# 2_pure60-WKL_matrix.net
KiCad netlist of a schematic drawn in Altium Designer
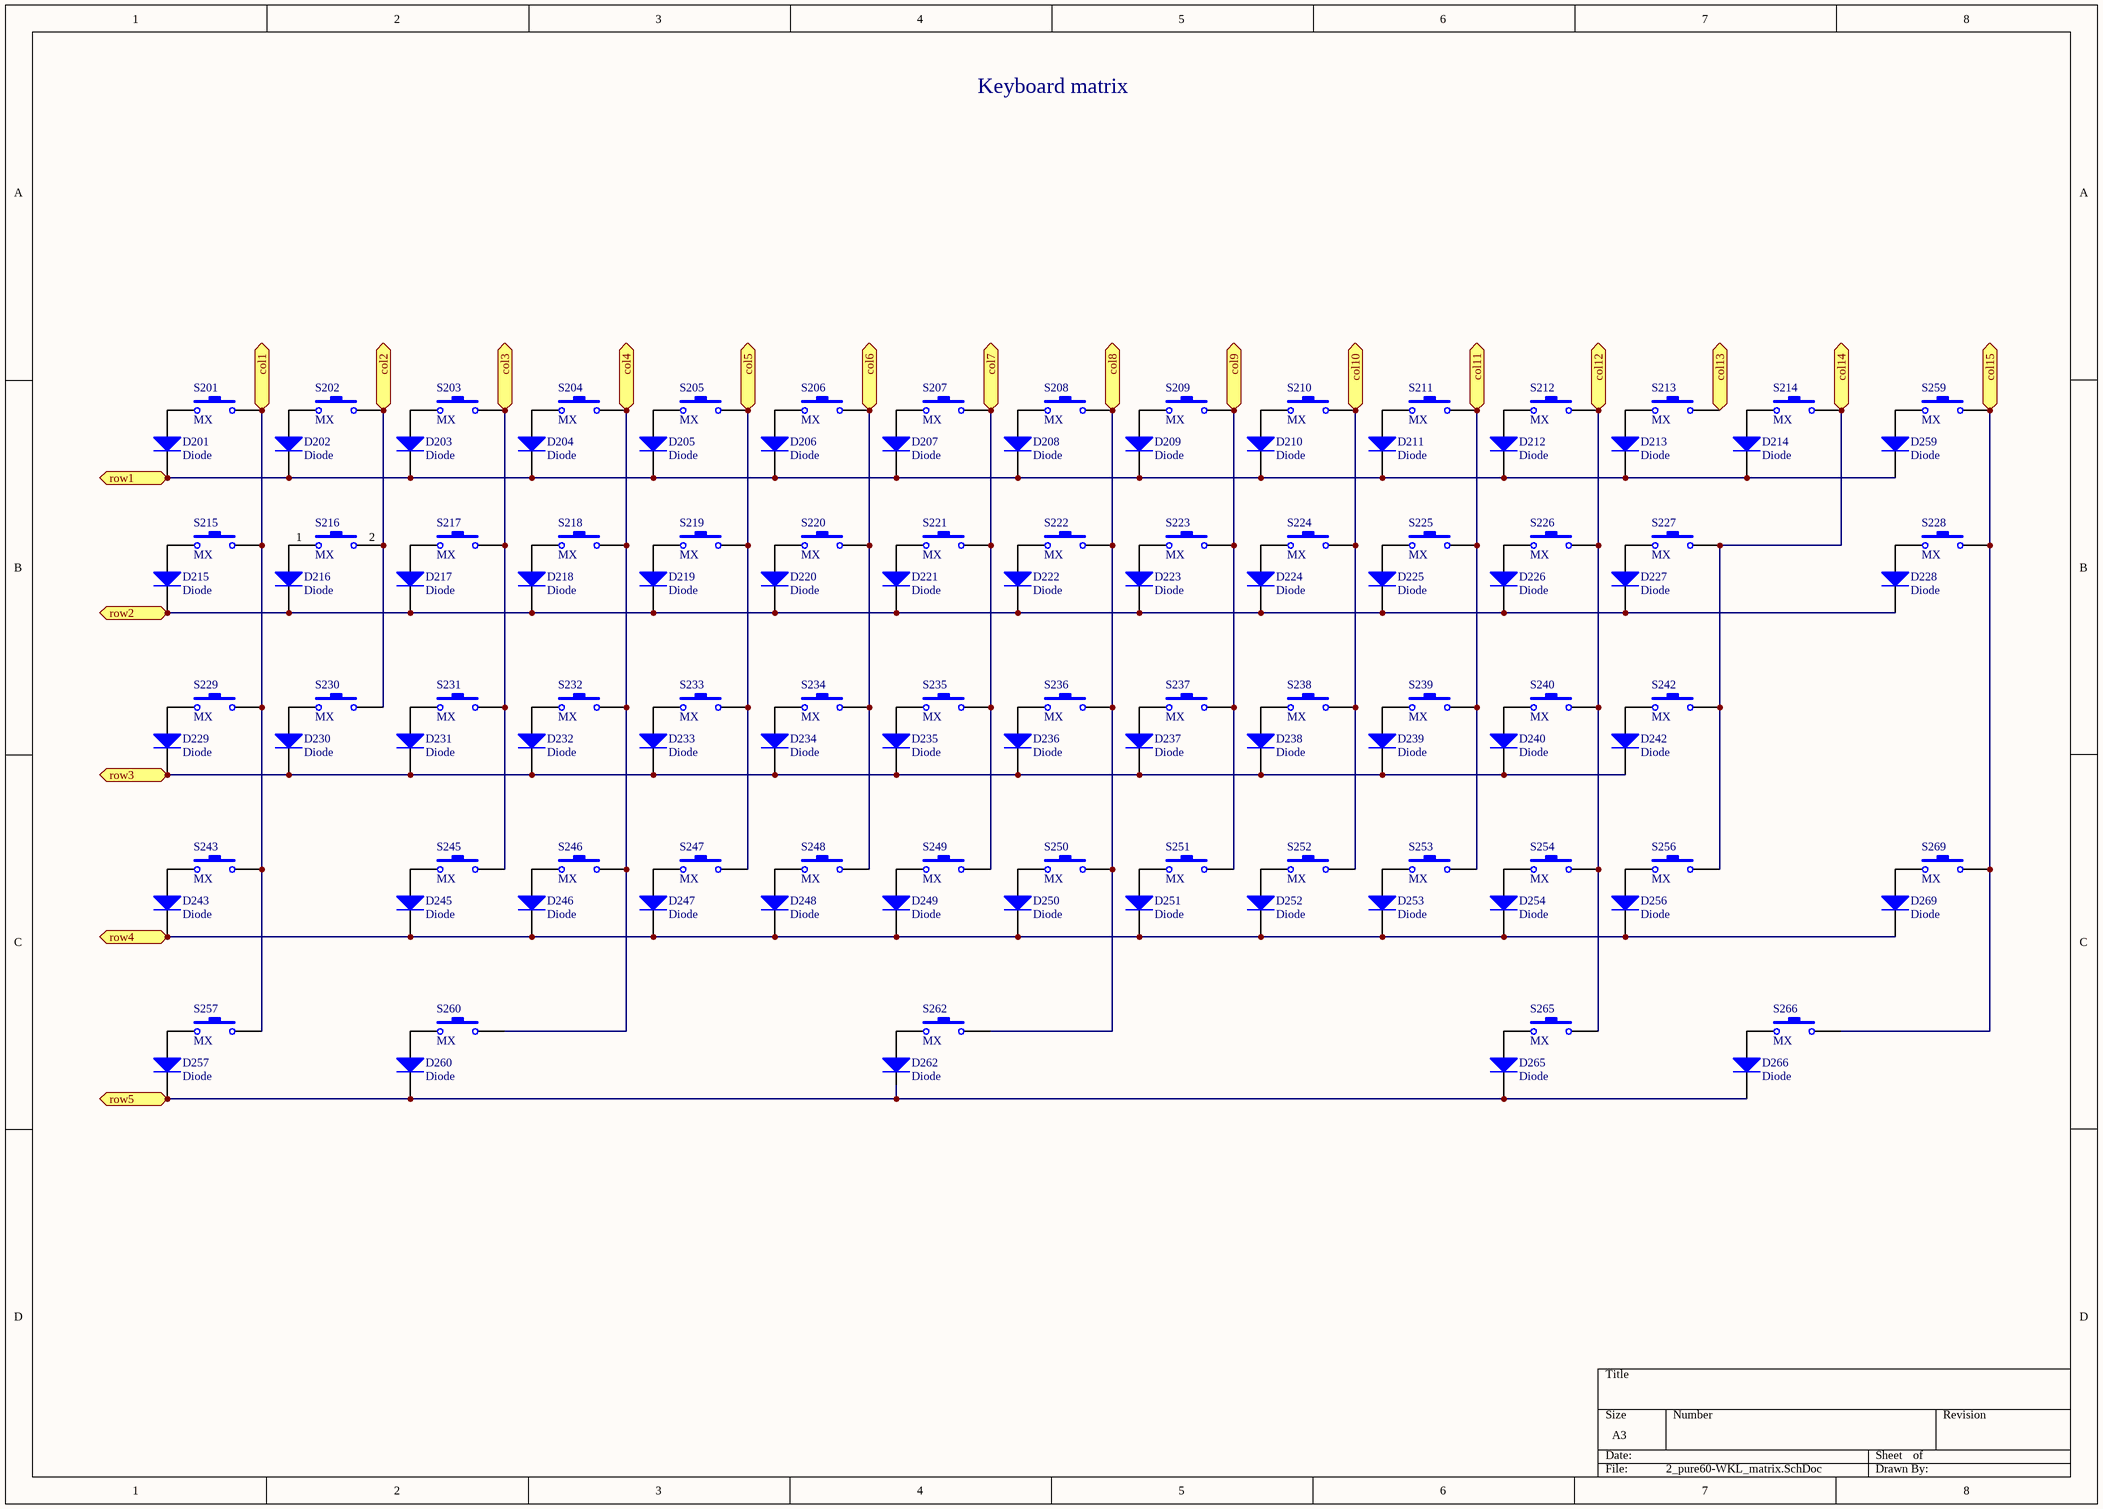
[diagram p0: 2_pure60-WKL_matrix.SchDoc]

(export (version "E")
  (design (tool "Eeschema 10.0.6"))
  (components
    (comp (ref "D201")
      (value "Diode")
      (footprint "D0603[1608]")
      (description "Default Diode")
      (fields (field (name "MFG") "Bourns Inc.") (field (name "MRF.PART") "CD4148WTP"))
      (libsource (lib "Miscellaneous Devices") (part "Diode"))
    )
    (comp (ref "D202")
      (value "Diode")
      (footprint "D0603[1608]")
      (description "Default Diode")
      (fields (field (name "MFG") "Bourns Inc.") (field (name "MRF.PART") "CD4148WTP"))
      (libsource (lib "Miscellaneous Devices") (part "Diode"))
    )
    (comp (ref "D203")
      (value "Diode")
      (footprint "D0603[1608]")
      (description "Default Diode")
      (fields (field (name "MFG") "Bourns Inc.") (field (name "MRF.PART") "CD4148WTP"))
      (libsource (lib "Miscellaneous Devices") (part "Diode"))
    )
    (comp (ref "D204")
      (value "Diode")
      (footprint "D0603[1608]")
      (description "Default Diode")
      (fields (field (name "MFG") "Bourns Inc.") (field (name "MRF.PART") "CD4148WTP"))
      (libsource (lib "Miscellaneous Devices") (part "Diode"))
    )
    (comp (ref "D205")
      (value "Diode")
      (footprint "D0603[1608]")
      (description "Default Diode")
      (fields (field (name "MFG") "Bourns Inc.") (field (name "MRF.PART") "CD4148WTP"))
      (libsource (lib "Miscellaneous Devices") (part "Diode"))
    )
    (comp (ref "D206")
      (value "Diode")
      (footprint "D0603[1608]")
      (description "Default Diode")
      (fields (field (name "MFG") "Bourns Inc.") (field (name "MRF.PART") "CD4148WTP"))
      (libsource (lib "Miscellaneous Devices") (part "Diode"))
    )
    (comp (ref "D207")
      (value "Diode")
      (footprint "D0603[1608]")
      (description "Default Diode")
      (fields (field (name "MFG") "Bourns Inc.") (field (name "MRF.PART") "CD4148WTP"))
      (libsource (lib "Miscellaneous Devices") (part "Diode"))
    )
    (comp (ref "D208")
      (value "Diode")
      (footprint "D0603[1608]")
      (description "Default Diode")
      (fields (field (name "MFG") "Bourns Inc.") (field (name "MRF.PART") "CD4148WTP"))
      (libsource (lib "Miscellaneous Devices") (part "Diode"))
    )
    (comp (ref "D209")
      (value "Diode")
      (footprint "D0603[1608]")
      (description "Default Diode")
      (fields (field (name "MFG") "Bourns Inc.") (field (name "MRF.PART") "CD4148WTP"))
      (libsource (lib "Miscellaneous Devices") (part "Diode"))
    )
    (comp (ref "D210")
      (value "Diode")
      (footprint "D0603[1608]")
      (description "Default Diode")
      (fields (field (name "MFG") "Bourns Inc.") (field (name "MRF.PART") "CD4148WTP"))
      (libsource (lib "Miscellaneous Devices") (part "Diode"))
    )
    (comp (ref "D211")
      (value "Diode")
      (footprint "D0603[1608]")
      (description "Default Diode")
      (fields (field (name "MFG") "Bourns Inc.") (field (name "MRF.PART") "CD4148WTP"))
      (libsource (lib "Miscellaneous Devices") (part "Diode"))
    )
    (comp (ref "D212")
      (value "Diode")
      (footprint "D0603[1608]")
      (description "Default Diode")
      (fields (field (name "MFG") "Bourns Inc.") (field (name "MRF.PART") "CD4148WTP"))
      (libsource (lib "Miscellaneous Devices") (part "Diode"))
    )
    (comp (ref "D213")
      (value "Diode")
      (footprint "D0603[1608]")
      (description "Default Diode")
      (fields (field (name "MFG") "Bourns Inc.") (field (name "MRF.PART") "CD4148WTP"))
      (libsource (lib "Miscellaneous Devices") (part "Diode"))
    )
    (comp (ref "D214")
      (value "Diode")
      (footprint "D0603[1608]")
      (description "Default Diode")
      (fields (field (name "MFG") "Bourns Inc.") (field (name "MRF.PART") "CD4148WTP"))
      (libsource (lib "Miscellaneous Devices") (part "Diode"))
    )
    (comp (ref "D215")
      (value "Diode")
      (footprint "D0603[1608]")
      (description "Default Diode")
      (fields (field (name "MFG") "Bourns Inc.") (field (name "MRF.PART") "CD4148WTP"))
      (libsource (lib "Miscellaneous Devices") (part "Diode"))
    )
    (comp (ref "D216")
      (value "Diode")
      (footprint "D0603[1608]")
      (description "Default Diode")
      (fields (field (name "MFG") "Bourns Inc.") (field (name "MRF.PART") "CD4148WTP"))
      (libsource (lib "Miscellaneous Devices") (part "Diode"))
    )
    (comp (ref "D217")
      (value "Diode")
      (footprint "D0603[1608]")
      (description "Default Diode")
      (fields (field (name "MFG") "Bourns Inc.") (field (name "MRF.PART") "CD4148WTP"))
      (libsource (lib "Miscellaneous Devices") (part "Diode"))
    )
    (comp (ref "D218")
      (value "Diode")
      (footprint "D0603[1608]")
      (description "Default Diode")
      (fields (field (name "MFG") "Bourns Inc.") (field (name "MRF.PART") "CD4148WTP"))
      (libsource (lib "Miscellaneous Devices") (part "Diode"))
    )
    (comp (ref "D219")
      (value "Diode")
      (footprint "D0603[1608]")
      (description "Default Diode")
      (fields (field (name "MFG") "Bourns Inc.") (field (name "MRF.PART") "CD4148WTP"))
      (libsource (lib "Miscellaneous Devices") (part "Diode"))
    )
    (comp (ref "D220")
      (value "Diode")
      (footprint "D0603[1608]")
      (description "Default Diode")
      (fields (field (name "MFG") "Bourns Inc.") (field (name "MRF.PART") "CD4148WTP"))
      (libsource (lib "Miscellaneous Devices") (part "Diode"))
    )
    (comp (ref "D221")
      (value "Diode")
      (footprint "D0603[1608]")
      (description "Default Diode")
      (fields (field (name "MFG") "Bourns Inc.") (field (name "MRF.PART") "CD4148WTP"))
      (libsource (lib "Miscellaneous Devices") (part "Diode"))
    )
    (comp (ref "D222")
      (value "Diode")
      (footprint "D0603[1608]")
      (description "Default Diode")
      (fields (field (name "MFG") "Bourns Inc.") (field (name "MRF.PART") "CD4148WTP"))
      (libsource (lib "Miscellaneous Devices") (part "Diode"))
    )
    (comp (ref "D223")
      (value "Diode")
      (footprint "D0603[1608]")
      (description "Default Diode")
      (fields (field (name "MFG") "Bourns Inc.") (field (name "MRF.PART") "CD4148WTP"))
      (libsource (lib "Miscellaneous Devices") (part "Diode"))
    )
    (comp (ref "D224")
      (value "Diode")
      (footprint "D0603[1608]")
      (description "Default Diode")
      (fields (field (name "MFG") "Bourns Inc.") (field (name "MRF.PART") "CD4148WTP"))
      (libsource (lib "Miscellaneous Devices") (part "Diode"))
    )
    (comp (ref "D225")
      (value "Diode")
      (footprint "D0603[1608]")
      (description "Default Diode")
      (fields (field (name "MFG") "Bourns Inc.") (field (name "MRF.PART") "CD4148WTP"))
      (libsource (lib "Miscellaneous Devices") (part "Diode"))
    )
    (comp (ref "D226")
      (value "Diode")
      (footprint "D0603[1608]")
      (description "Default Diode")
      (fields (field (name "MFG") "Bourns Inc.") (field (name "MRF.PART") "CD4148WTP"))
      (libsource (lib "Miscellaneous Devices") (part "Diode"))
    )
    (comp (ref "D227")
      (value "Diode")
      (footprint "D0603[1608]")
      (description "Default Diode")
      (fields (field (name "MFG") "Bourns Inc.") (field (name "MRF.PART") "CD4148WTP"))
      (libsource (lib "Miscellaneous Devices") (part "Diode"))
    )
    (comp (ref "D228")
      (value "Diode")
      (footprint "D0603[1608]")
      (description "Default Diode")
      (fields (field (name "MFG") "Bourns Inc.") (field (name "MRF.PART") "CD4148WTP"))
      (libsource (lib "Miscellaneous Devices") (part "Diode"))
    )
    (comp (ref "D229")
      (value "Diode")
      (footprint "D0603[1608]")
      (description "Default Diode")
      (fields (field (name "MFG") "Bourns Inc.") (field (name "MRF.PART") "CD4148WTP"))
      (libsource (lib "Miscellaneous Devices") (part "Diode"))
    )
    (comp (ref "D230")
      (value "Diode")
      (footprint "D0603[1608]")
      (description "Default Diode")
      (fields (field (name "MFG") "Bourns Inc.") (field (name "MRF.PART") "CD4148WTP"))
      (libsource (lib "Miscellaneous Devices") (part "Diode"))
    )
    (comp (ref "D231")
      (value "Diode")
      (footprint "D0603[1608]")
      (description "Default Diode")
      (fields (field (name "MFG") "Bourns Inc.") (field (name "MRF.PART") "CD4148WTP"))
      (libsource (lib "Miscellaneous Devices") (part "Diode"))
    )
    (comp (ref "D232")
      (value "Diode")
      (footprint "D0603[1608]")
      (description "Default Diode")
      (fields (field (name "MFG") "Bourns Inc.") (field (name "MRF.PART") "CD4148WTP"))
      (libsource (lib "Miscellaneous Devices") (part "Diode"))
    )
    (comp (ref "D233")
      (value "Diode")
      (footprint "D0603[1608]")
      (description "Default Diode")
      (fields (field (name "MFG") "Bourns Inc.") (field (name "MRF.PART") "CD4148WTP"))
      (libsource (lib "Miscellaneous Devices") (part "Diode"))
    )
    (comp (ref "D234")
      (value "Diode")
      (footprint "D0603[1608]")
      (description "Default Diode")
      (fields (field (name "MFG") "Bourns Inc.") (field (name "MRF.PART") "CD4148WTP"))
      (libsource (lib "Miscellaneous Devices") (part "Diode"))
    )
    (comp (ref "D235")
      (value "Diode")
      (footprint "D0603[1608]")
      (description "Default Diode")
      (fields (field (name "MFG") "Bourns Inc.") (field (name "MRF.PART") "CD4148WTP"))
      (libsource (lib "Miscellaneous Devices") (part "Diode"))
    )
    (comp (ref "D236")
      (value "Diode")
      (footprint "D0603[1608]")
      (description "Default Diode")
      (fields (field (name "MFG") "Bourns Inc.") (field (name "MRF.PART") "CD4148WTP"))
      (libsource (lib "Miscellaneous Devices") (part "Diode"))
    )
    (comp (ref "D237")
      (value "Diode")
      (footprint "D0603[1608]")
      (description "Default Diode")
      (fields (field (name "MFG") "Bourns Inc.") (field (name "MRF.PART") "CD4148WTP"))
      (libsource (lib "Miscellaneous Devices") (part "Diode"))
    )
    (comp (ref "D238")
      (value "Diode")
      (footprint "D0603[1608]")
      (description "Default Diode")
      (fields (field (name "MFG") "Bourns Inc.") (field (name "MRF.PART") "CD4148WTP"))
      (libsource (lib "Miscellaneous Devices") (part "Diode"))
    )
    (comp (ref "D239")
      (value "Diode")
      (footprint "D0603[1608]")
      (description "Default Diode")
      (fields (field (name "MFG") "Bourns Inc.") (field (name "MRF.PART") "CD4148WTP"))
      (libsource (lib "Miscellaneous Devices") (part "Diode"))
    )
    (comp (ref "D240")
      (value "Diode")
      (footprint "D0603[1608]")
      (description "Default Diode")
      (fields (field (name "MFG") "Bourns Inc.") (field (name "MRF.PART") "CD4148WTP"))
      (libsource (lib "Miscellaneous Devices") (part "Diode"))
    )
    (comp (ref "D242")
      (value "Diode")
      (footprint "D0603[1608]")
      (description "Default Diode")
      (fields (field (name "MFG") "Bourns Inc.") (field (name "MRF.PART") "CD4148WTP"))
      (libsource (lib "Miscellaneous Devices") (part "Diode"))
    )
    (comp (ref "D243")
      (value "Diode")
      (footprint "D0603[1608]")
      (description "Default Diode")
      (fields (field (name "MFG") "Bourns Inc.") (field (name "MRF.PART") "CD4148WTP"))
      (libsource (lib "Miscellaneous Devices") (part "Diode"))
    )
    (comp (ref "D245")
      (value "Diode")
      (footprint "D0603[1608]")
      (description "Default Diode")
      (fields (field (name "MFG") "Bourns Inc.") (field (name "MRF.PART") "CD4148WTP"))
      (libsource (lib "Miscellaneous Devices") (part "Diode"))
    )
    (comp (ref "D246")
      (value "Diode")
      (footprint "D0603[1608]")
      (description "Default Diode")
      (fields (field (name "MFG") "Bourns Inc.") (field (name "MRF.PART") "CD4148WTP"))
      (libsource (lib "Miscellaneous Devices") (part "Diode"))
    )
    (comp (ref "D247")
      (value "Diode")
      (footprint "D0603[1608]")
      (description "Default Diode")
      (fields (field (name "MFG") "Bourns Inc.") (field (name "MRF.PART") "CD4148WTP"))
      (libsource (lib "Miscellaneous Devices") (part "Diode"))
    )
    (comp (ref "D248")
      (value "Diode")
      (footprint "D0603[1608]")
      (description "Default Diode")
      (fields (field (name "MFG") "Bourns Inc.") (field (name "MRF.PART") "CD4148WTP"))
      (libsource (lib "Miscellaneous Devices") (part "Diode"))
    )
    (comp (ref "D249")
      (value "Diode")
      (footprint "D0603[1608]")
      (description "Default Diode")
      (fields (field (name "MFG") "Bourns Inc.") (field (name "MRF.PART") "CD4148WTP"))
      (libsource (lib "Miscellaneous Devices") (part "Diode"))
    )
    (comp (ref "D250")
      (value "Diode")
      (footprint "D0603[1608]")
      (description "Default Diode")
      (fields (field (name "MFG") "Bourns Inc.") (field (name "MRF.PART") "CD4148WTP"))
      (libsource (lib "Miscellaneous Devices") (part "Diode"))
    )
    (comp (ref "D251")
      (value "Diode")
      (footprint "D0603[1608]")
      (description "Default Diode")
      (fields (field (name "MFG") "Bourns Inc.") (field (name "MRF.PART") "CD4148WTP"))
      (libsource (lib "Miscellaneous Devices") (part "Diode"))
    )
    (comp (ref "D252")
      (value "Diode")
      (footprint "D0603[1608]")
      (description "Default Diode")
      (fields (field (name "MFG") "Bourns Inc.") (field (name "MRF.PART") "CD4148WTP"))
      (libsource (lib "Miscellaneous Devices") (part "Diode"))
    )
    (comp (ref "D253")
      (value "Diode")
      (footprint "D0603[1608]")
      (description "Default Diode")
      (fields (field (name "MFG") "Bourns Inc.") (field (name "MRF.PART") "CD4148WTP"))
      (libsource (lib "Miscellaneous Devices") (part "Diode"))
    )
    (comp (ref "D254")
      (value "Diode")
      (footprint "D0603[1608]")
      (description "Default Diode")
      (fields (field (name "MFG") "Bourns Inc.") (field (name "MRF.PART") "CD4148WTP"))
      (libsource (lib "Miscellaneous Devices") (part "Diode"))
    )
    (comp (ref "D256")
      (value "Diode")
      (footprint "D0603[1608]")
      (description "Default Diode")
      (fields (field (name "MFG") "Bourns Inc.") (field (name "MRF.PART") "CD4148WTP"))
      (libsource (lib "Miscellaneous Devices") (part "Diode"))
    )
    (comp (ref "D257")
      (value "Diode")
      (footprint "D0603[1608]")
      (description "Default Diode")
      (fields (field (name "MFG") "Bourns Inc.") (field (name "MRF.PART") "CD4148WTP"))
      (libsource (lib "Miscellaneous Devices") (part "Diode"))
    )
    (comp (ref "D259")
      (value "Diode")
      (footprint "D0603[1608]")
      (description "Default Diode")
      (fields (field (name "MFG") "Bourns Inc.") (field (name "MRF.PART") "CD4148WTP"))
      (libsource (lib "Miscellaneous Devices") (part "Diode"))
    )
    (comp (ref "D260")
      (value "Diode")
      (footprint "D0603[1608]")
      (description "Default Diode")
      (fields (field (name "MFG") "Bourns Inc.") (field (name "MRF.PART") "CD4148WTP"))
      (libsource (lib "Miscellaneous Devices") (part "Diode"))
    )
    (comp (ref "D262")
      (value "Diode")
      (footprint "D0603[1608]")
      (description "Default Diode")
      (fields (field (name "MFG") "Bourns Inc.") (field (name "MRF.PART") "CD4148WTP"))
      (libsource (lib "Miscellaneous Devices") (part "Diode"))
    )
    (comp (ref "D265")
      (value "Diode")
      (footprint "D0603[1608]")
      (description "Default Diode")
      (fields (field (name "MFG") "Bourns Inc.") (field (name "MRF.PART") "CD4148WTP"))
      (libsource (lib "Miscellaneous Devices") (part "Diode"))
    )
    (comp (ref "D266")
      (value "Diode")
      (footprint "D0603[1608]")
      (description "Default Diode")
      (fields (field (name "MFG") "Bourns Inc.") (field (name "MRF.PART") "CD4148WTP"))
      (libsource (lib "Miscellaneous Devices") (part "Diode"))
    )
    (comp (ref "D269")
      (value "Diode")
      (footprint "D0603[1608]")
      (description "Default Diode")
      (fields (field (name "MFG") "Bourns Inc.") (field (name "MRF.PART") "CD4148WTP"))
      (libsource (lib "Miscellaneous Devices") (part "Diode"))
    )
    (comp (ref "S201")
      (value "MX")
      (footprint "MX-switch - switched pol")
      (description "Switch")
      (libsource (lib "Miscellaneous Devices") (part "SW-PB"))
    )
    (comp (ref "S202")
      (value "MX")
      (footprint "MX-switch - switched pol")
      (description "Switch")
      (libsource (lib "Miscellaneous Devices") (part "SW-PB"))
    )
    (comp (ref "S203")
      (value "MX")
      (footprint "MX-switch - switched pol")
      (description "Switch")
      (libsource (lib "Miscellaneous Devices") (part "SW-PB"))
    )
    (comp (ref "S204")
      (value "MX")
      (footprint "MX-switch - switched pol")
      (description "Switch")
      (libsource (lib "Miscellaneous Devices") (part "SW-PB"))
    )
    (comp (ref "S205")
      (value "MX")
      (footprint "MX-switch - switched pol")
      (description "Switch")
      (libsource (lib "Miscellaneous Devices") (part "SW-PB"))
    )
    (comp (ref "S206")
      (value "MX")
      (footprint "MX-switch - switched pol")
      (description "Switch")
      (libsource (lib "Miscellaneous Devices") (part "SW-PB"))
    )
    (comp (ref "S207")
      (value "MX")
      (footprint "MX-switch - switched pol")
      (description "Switch")
      (libsource (lib "Miscellaneous Devices") (part "SW-PB"))
    )
    (comp (ref "S208")
      (value "MX")
      (footprint "MX-switch - switched pol")
      (description "Switch")
      (libsource (lib "Miscellaneous Devices") (part "SW-PB"))
    )
    (comp (ref "S209")
      (value "MX")
      (footprint "MX-switch - switched pol")
      (description "Switch")
      (libsource (lib "Miscellaneous Devices") (part "SW-PB"))
    )
    (comp (ref "S210")
      (value "MX")
      (footprint "MX-switch - switched pol")
      (description "Switch")
      (libsource (lib "Miscellaneous Devices") (part "SW-PB"))
    )
    (comp (ref "S211")
      (value "MX")
      (footprint "MX-switch - switched pol")
      (description "Switch")
      (libsource (lib "Miscellaneous Devices") (part "SW-PB"))
    )
    (comp (ref "S212")
      (value "MX")
      (footprint "MX-switch - switched pol")
      (description "Switch")
      (libsource (lib "Miscellaneous Devices") (part "SW-PB"))
    )
    (comp (ref "S213")
      (value "MX")
      (footprint "MX-switch - switched pol")
      (description "Switch")
      (libsource (lib "Miscellaneous Devices") (part "SW-PB"))
    )
    (comp (ref "S214")
      (value "MX")
      (footprint "MX-switch - switched pol")
      (description "Switch")
      (libsource (lib "Miscellaneous Devices") (part "SW-PB"))
    )
    (comp (ref "S215")
      (value "MX")
      (footprint "MX-switch - 1.5U - switched pol")
      (description "TAB")
      (libsource (lib "Miscellaneous Devices") (part "SW-PB"))
    )
    (comp (ref "S216")
      (value "MX")
      (footprint "MX-switch - switched pol")
      (description "Switch")
      (libsource (lib "") (part "SW-PB_1"))
    )
    (comp (ref "S217")
      (value "MX")
      (footprint "MX-switch - switched pol")
      (description "Switch")
      (libsource (lib "Miscellaneous Devices") (part "SW-PB"))
    )
    (comp (ref "S218")
      (value "MX")
      (footprint "MX-switch - switched pol")
      (description "Switch")
      (libsource (lib "Miscellaneous Devices") (part "SW-PB"))
    )
    (comp (ref "S219")
      (value "MX")
      (footprint "MX-switch - switched pol")
      (description "Switch")
      (libsource (lib "Miscellaneous Devices") (part "SW-PB"))
    )
    (comp (ref "S220")
      (value "MX")
      (footprint "MX-switch - switched pol")
      (description "Switch")
      (libsource (lib "Miscellaneous Devices") (part "SW-PB"))
    )
    (comp (ref "S221")
      (value "MX")
      (footprint "MX-switch - switched pol")
      (description "Switch")
      (libsource (lib "Miscellaneous Devices") (part "SW-PB"))
    )
    (comp (ref "S222")
      (value "MX")
      (footprint "MX-switch - switched pol")
      (description "Switch")
      (libsource (lib "Miscellaneous Devices") (part "SW-PB"))
    )
    (comp (ref "S223")
      (value "MX")
      (footprint "MX-switch - switched pol")
      (description "Switch")
      (libsource (lib "Miscellaneous Devices") (part "SW-PB"))
    )
    (comp (ref "S224")
      (value "MX")
      (footprint "MX-switch - switched pol")
      (description "Switch")
      (libsource (lib "Miscellaneous Devices") (part "SW-PB"))
    )
    (comp (ref "S225")
      (value "MX")
      (footprint "MX-switch - switched pol")
      (description "Switch")
      (libsource (lib "Miscellaneous Devices") (part "SW-PB"))
    )
    (comp (ref "S226")
      (value "MX")
      (footprint "MX-switch - switched pol")
      (description "Switch")
      (libsource (lib "Miscellaneous Devices") (part "SW-PB"))
    )
    (comp (ref "S227")
      (value "MX")
      (footprint "MX-switch - switched pol")
      (description "Switch")
      (libsource (lib "Miscellaneous Devices") (part "SW-PB"))
    )
    (comp (ref "S228")
      (value "MX")
      (footprint "MX-switch - 1.5U")
      (description "Switch")
      (libsource (lib "Miscellaneous Devices") (part "SW-PB"))
    )
    (comp (ref "S229")
      (value "MX")
      (footprint "MX-switch - CAPS - stepped")
      (description "Switch")
      (libsource (lib "Miscellaneous Devices") (part "SW-PB"))
    )
    (comp (ref "S230")
      (value "MX")
      (footprint "MX-switch - switched pol")
      (description "Switch")
      (libsource (lib "Miscellaneous Devices") (part "SW-PB"))
    )
    (comp (ref "S231")
      (value "MX")
      (footprint "MX-switch - switched pol")
      (description "Switch")
      (libsource (lib "Miscellaneous Devices") (part "SW-PB"))
    )
    (comp (ref "S232")
      (value "MX")
      (footprint "MX-switch - switched pol")
      (description "Switch")
      (libsource (lib "Miscellaneous Devices") (part "SW-PB"))
    )
    (comp (ref "S233")
      (value "MX")
      (footprint "MX-switch - switched pol")
      (description "Switch")
      (libsource (lib "Miscellaneous Devices") (part "SW-PB"))
    )
    (comp (ref "S234")
      (value "MX")
      (footprint "MX-switch - switched pol")
      (description "Switch")
      (libsource (lib "Miscellaneous Devices") (part "SW-PB"))
    )
    (comp (ref "S235")
      (value "MX")
      (footprint "MX-switch - switched pol")
      (description "Switch")
      (libsource (lib "Miscellaneous Devices") (part "SW-PB"))
    )
    (comp (ref "S236")
      (value "MX")
      (footprint "MX-switch - switched pol")
      (description "Switch")
      (libsource (lib "Miscellaneous Devices") (part "SW-PB"))
    )
    (comp (ref "S237")
      (value "MX")
      (footprint "MX-switch - switched pol")
      (description "Switch")
      (libsource (lib "Miscellaneous Devices") (part "SW-PB"))
    )
    (comp (ref "S238")
      (value "MX")
      (footprint "MX-switch - switched pol")
      (description "Switch")
      (libsource (lib "Miscellaneous Devices") (part "SW-PB"))
    )
    (comp (ref "S239")
      (value "MX")
      (footprint "MX-switch - switched pol")
      (description "Switch")
      (libsource (lib "Miscellaneous Devices") (part "SW-PB"))
    )
    (comp (ref "S240")
      (value "MX")
      (footprint "MX-switch - switched pol")
      (description "Switch")
      (libsource (lib "Miscellaneous Devices") (part "SW-PB"))
    )
    (comp (ref "S242")
      (value "MX")
      (footprint "MX-switch - Enter_ANSI")
      (description "Switch")
      (libsource (lib "Miscellaneous Devices") (part "SW-PB"))
    )
    (comp (ref "S243")
      (value "MX")
      (footprint "MX-switch - 2.25U")
      (description "Switch")
      (libsource (lib "Miscellaneous Devices") (part "SW-PB"))
    )
    (comp (ref "S245")
      (value "MX")
      (footprint "MX-switch - switched pol")
      (description "Switch")
      (libsource (lib "Miscellaneous Devices") (part "SW-PB"))
    )
    (comp (ref "S246")
      (value "MX")
      (footprint "MX-switch - switched pol")
      (description "Switch")
      (libsource (lib "Miscellaneous Devices") (part "SW-PB"))
    )
    (comp (ref "S247")
      (value "MX")
      (footprint "MX-switch - switched pol")
      (description "Switch")
      (libsource (lib "Miscellaneous Devices") (part "SW-PB"))
    )
    (comp (ref "S248")
      (value "MX")
      (footprint "MX-switch - switched pol")
      (description "Switch")
      (libsource (lib "Miscellaneous Devices") (part "SW-PB"))
    )
    (comp (ref "S249")
      (value "MX")
      (footprint "MX-switch - switched pol")
      (description "Switch")
      (libsource (lib "Miscellaneous Devices") (part "SW-PB"))
    )
    (comp (ref "S250")
      (value "MX")
      (footprint "MX-switch - switched pol")
      (description "Switch")
      (libsource (lib "Miscellaneous Devices") (part "SW-PB"))
    )
    (comp (ref "S251")
      (value "MX")
      (footprint "MX-switch - switched pol")
      (description "Switch")
      (libsource (lib "Miscellaneous Devices") (part "SW-PB"))
    )
    (comp (ref "S252")
      (value "MX")
      (footprint "MX-switch - switched pol")
      (description "Switch")
      (libsource (lib "Miscellaneous Devices") (part "SW-PB"))
    )
    (comp (ref "S253")
      (value "MX")
      (footprint "MX-switch - switched pol")
      (description "Switch")
      (libsource (lib "Miscellaneous Devices") (part "SW-PB"))
    )
    (comp (ref "S254")
      (value "MX")
      (footprint "MX-switch - switched pol")
      (description "Switch")
      (libsource (lib "Miscellaneous Devices") (part "SW-PB"))
    )
    (comp (ref "S256")
      (value "MX")
      (footprint "MX-switch - 1.75")
      (description "Switch")
      (libsource (lib "Miscellaneous Devices") (part "SW-PB"))
    )
    (comp (ref "S257")
      (value "MX")
      (footprint "MX-switch - 1.5U")
      (description "Switch")
      (libsource (lib "Miscellaneous Devices") (part "SW-PB"))
    )
    (comp (ref "S259")
      (value "MX")
      (footprint "MX-switch")
      (description "Switch")
      (libsource (lib "Miscellaneous Devices") (part "SW-PB"))
    )
    (comp (ref "S260")
      (value "MX")
      (footprint "MX-switch - 1.5U")
      (description "Switch")
      (libsource (lib "Miscellaneous Devices") (part "SW-PB"))
    )
    (comp (ref "S262")
      (value "MX")
      (footprint "MX-switch - 7u space")
      (description "Switch")
      (libsource (lib "Miscellaneous Devices") (part "SW-PB"))
    )
    (comp (ref "S265")
      (value "MX")
      (footprint "MX-switch - 1.5U")
      (description "Switch")
      (libsource (lib "Miscellaneous Devices") (part "SW-PB"))
    )
    (comp (ref "S266")
      (value "MX")
      (footprint "MX-switch - 1.5U")
      (description "Switch")
      (libsource (lib "Miscellaneous Devices") (part "SW-PB"))
    )
    (comp (ref "S269")
      (value "MX")
      (footprint "MX-switch")
      (description "Switch")
      (libsource (lib "Miscellaneous Devices") (part "SW-PB"))
    )
  )
  (nets
    (net (code "1") (name "/col1") (class "Default")
      (node (ref "S201") (pin "2") (pinfunction "2_2") (pintype "passive"))
      (node (ref "S215") (pin "2") (pinfunction "2_2") (pintype "passive"))
      (node (ref "S229") (pin "2") (pinfunction "2_2") (pintype "passive"))
      (node (ref "S243") (pin "2") (pinfunction "2_2") (pintype "passive"))
      (node (ref "S257") (pin "2") (pinfunction "2_2") (pintype "passive"))
    )
    (net (code "2") (name "/col2") (class "Default")
      (node (ref "S202") (pin "2") (pinfunction "2_2") (pintype "passive"))
      (node (ref "S216") (pin "2") (pinfunction "2_2") (pintype "passive"))
      (node (ref "S230") (pin "2") (pinfunction "2_2") (pintype "passive"))
    )
    (net (code "3") (name "/col3") (class "Default")
      (node (ref "S203") (pin "2") (pinfunction "2_2") (pintype "passive"))
      (node (ref "S217") (pin "2") (pinfunction "2_2") (pintype "passive"))
      (node (ref "S231") (pin "2") (pinfunction "2_2") (pintype "passive"))
      (node (ref "S245") (pin "2") (pinfunction "2_2") (pintype "passive"))
    )
    (net (code "4") (name "/col4") (class "Default")
      (node (ref "S204") (pin "2") (pinfunction "2_2") (pintype "passive"))
      (node (ref "S218") (pin "2") (pinfunction "2_2") (pintype "passive"))
      (node (ref "S232") (pin "2") (pinfunction "2_2") (pintype "passive"))
      (node (ref "S246") (pin "2") (pinfunction "2_2") (pintype "passive"))
      (node (ref "S260") (pin "2") (pinfunction "2_2") (pintype "passive"))
    )
    (net (code "5") (name "/col5") (class "Default")
      (node (ref "S205") (pin "2") (pinfunction "2_2") (pintype "passive"))
      (node (ref "S219") (pin "2") (pinfunction "2_2") (pintype "passive"))
      (node (ref "S233") (pin "2") (pinfunction "2_2") (pintype "passive"))
      (node (ref "S247") (pin "2") (pinfunction "2_2") (pintype "passive"))
    )
    (net (code "6") (name "/col6") (class "Default")
      (node (ref "S206") (pin "2") (pinfunction "2_2") (pintype "passive"))
      (node (ref "S220") (pin "2") (pinfunction "2_2") (pintype "passive"))
      (node (ref "S234") (pin "2") (pinfunction "2_2") (pintype "passive"))
      (node (ref "S248") (pin "2") (pinfunction "2_2") (pintype "passive"))
    )
    (net (code "7") (name "/col7") (class "Default")
      (node (ref "S207") (pin "2") (pinfunction "2_2") (pintype "passive"))
      (node (ref "S221") (pin "2") (pinfunction "2_2") (pintype "passive"))
      (node (ref "S235") (pin "2") (pinfunction "2_2") (pintype "passive"))
      (node (ref "S249") (pin "2") (pinfunction "2_2") (pintype "passive"))
    )
    (net (code "8") (name "/col8") (class "Default")
      (node (ref "S208") (pin "2") (pinfunction "2_2") (pintype "passive"))
      (node (ref "S222") (pin "2") (pinfunction "2_2") (pintype "passive"))
      (node (ref "S236") (pin "2") (pinfunction "2_2") (pintype "passive"))
      (node (ref "S250") (pin "2") (pinfunction "2_2") (pintype "passive"))
      (node (ref "S262") (pin "2") (pinfunction "2_2") (pintype "passive"))
    )
    (net (code "9") (name "/col9") (class "Default")
      (node (ref "S209") (pin "2") (pinfunction "2_2") (pintype "passive"))
      (node (ref "S223") (pin "2") (pinfunction "2_2") (pintype "passive"))
      (node (ref "S237") (pin "2") (pinfunction "2_2") (pintype "passive"))
      (node (ref "S251") (pin "2") (pinfunction "2_2") (pintype "passive"))
    )
    (net (code "10") (name "/col10") (class "Default")
      (node (ref "S210") (pin "2") (pinfunction "2_2") (pintype "passive"))
      (node (ref "S224") (pin "2") (pinfunction "2_2") (pintype "passive"))
      (node (ref "S238") (pin "2") (pinfunction "2_2") (pintype "passive"))
      (node (ref "S252") (pin "2") (pinfunction "2_2") (pintype "passive"))
    )
    (net (code "11") (name "/col11") (class "Default")
      (node (ref "S211") (pin "2") (pinfunction "2_2") (pintype "passive"))
      (node (ref "S225") (pin "2") (pinfunction "2_2") (pintype "passive"))
      (node (ref "S239") (pin "2") (pinfunction "2_2") (pintype "passive"))
      (node (ref "S253") (pin "2") (pinfunction "2_2") (pintype "passive"))
    )
    (net (code "12") (name "/col12") (class "Default")
      (node (ref "S212") (pin "2") (pinfunction "2_2") (pintype "passive"))
      (node (ref "S226") (pin "2") (pinfunction "2_2") (pintype "passive"))
      (node (ref "S240") (pin "2") (pinfunction "2_2") (pintype "passive"))
      (node (ref "S254") (pin "2") (pinfunction "2_2") (pintype "passive"))
      (node (ref "S265") (pin "2") (pinfunction "2_2") (pintype "passive"))
    )
    (net (code "13") (name "/col13") (class "Default")
      (node (ref "S213") (pin "2") (pinfunction "2_2") (pintype "passive"))
    )
    (net (code "14") (name "/col14") (class "Default")
      (node (ref "S214") (pin "2") (pinfunction "2_2") (pintype "passive"))
      (node (ref "S227") (pin "2") (pinfunction "2_2") (pintype "passive"))
      (node (ref "S242") (pin "2") (pinfunction "2_2") (pintype "passive"))
      (node (ref "S256") (pin "2") (pinfunction "2_2") (pintype "passive"))
    )
    (net (code "15") (name "/col15") (class "Default")
      (node (ref "S228") (pin "2") (pinfunction "2_2") (pintype "passive"))
      (node (ref "S259") (pin "2") (pinfunction "2_2") (pintype "passive"))
      (node (ref "S266") (pin "2") (pinfunction "2_2") (pintype "passive"))
      (node (ref "S269") (pin "2") (pinfunction "2_2") (pintype "passive"))
    )
    (net (code "16") (name "/row1") (class "Default")
      (node (ref "D201") (pin "2") (pinfunction "K_2") (pintype "passive"))
      (node (ref "D202") (pin "2") (pinfunction "K_2") (pintype "passive"))
      (node (ref "D203") (pin "2") (pinfunction "K_2") (pintype "passive"))
      (node (ref "D204") (pin "2") (pinfunction "K_2") (pintype "passive"))
      (node (ref "D205") (pin "2") (pinfunction "K_2") (pintype "passive"))
      (node (ref "D206") (pin "2") (pinfunction "K_2") (pintype "passive"))
      (node (ref "D207") (pin "2") (pinfunction "K_2") (pintype "passive"))
      (node (ref "D208") (pin "2") (pinfunction "K_2") (pintype "passive"))
      (node (ref "D209") (pin "2") (pinfunction "K_2") (pintype "passive"))
      (node (ref "D210") (pin "2") (pinfunction "K_2") (pintype "passive"))
      (node (ref "D211") (pin "2") (pinfunction "K_2") (pintype "passive"))
      (node (ref "D212") (pin "2") (pinfunction "K_2") (pintype "passive"))
      (node (ref "D213") (pin "2") (pinfunction "K_2") (pintype "passive"))
      (node (ref "D214") (pin "2") (pinfunction "K_2") (pintype "passive"))
      (node (ref "D259") (pin "2") (pinfunction "K_2") (pintype "passive"))
    )
    (net (code "17") (name "/row2") (class "Default")
      (node (ref "D215") (pin "2") (pinfunction "K_2") (pintype "passive"))
      (node (ref "D216") (pin "2") (pinfunction "K_2") (pintype "passive"))
      (node (ref "D217") (pin "2") (pinfunction "K_2") (pintype "passive"))
      (node (ref "D218") (pin "2") (pinfunction "K_2") (pintype "passive"))
      (node (ref "D219") (pin "2") (pinfunction "K_2") (pintype "passive"))
      (node (ref "D220") (pin "2") (pinfunction "K_2") (pintype "passive"))
      (node (ref "D221") (pin "2") (pinfunction "K_2") (pintype "passive"))
      (node (ref "D222") (pin "2") (pinfunction "K_2") (pintype "passive"))
      (node (ref "D223") (pin "2") (pinfunction "K_2") (pintype "passive"))
      (node (ref "D224") (pin "2") (pinfunction "K_2") (pintype "passive"))
      (node (ref "D225") (pin "2") (pinfunction "K_2") (pintype "passive"))
      (node (ref "D226") (pin "2") (pinfunction "K_2") (pintype "passive"))
      (node (ref "D227") (pin "2") (pinfunction "K_2") (pintype "passive"))
      (node (ref "D228") (pin "2") (pinfunction "K_2") (pintype "passive"))
    )
    (net (code "18") (name "/row3") (class "Default")
      (node (ref "D229") (pin "2") (pinfunction "K_2") (pintype "passive"))
      (node (ref "D230") (pin "2") (pinfunction "K_2") (pintype "passive"))
      (node (ref "D231") (pin "2") (pinfunction "K_2") (pintype "passive"))
      (node (ref "D232") (pin "2") (pinfunction "K_2") (pintype "passive"))
      (node (ref "D233") (pin "2") (pinfunction "K_2") (pintype "passive"))
      (node (ref "D234") (pin "2") (pinfunction "K_2") (pintype "passive"))
      (node (ref "D235") (pin "2") (pinfunction "K_2") (pintype "passive"))
      (node (ref "D236") (pin "2") (pinfunction "K_2") (pintype "passive"))
      (node (ref "D237") (pin "2") (pinfunction "K_2") (pintype "passive"))
      (node (ref "D238") (pin "2") (pinfunction "K_2") (pintype "passive"))
      (node (ref "D239") (pin "2") (pinfunction "K_2") (pintype "passive"))
      (node (ref "D240") (pin "2") (pinfunction "K_2") (pintype "passive"))
      (node (ref "D242") (pin "2") (pinfunction "K_2") (pintype "passive"))
    )
    (net (code "19") (name "/row4") (class "Default")
      (node (ref "D243") (pin "2") (pinfunction "K_2") (pintype "passive"))
      (node (ref "D245") (pin "2") (pinfunction "K_2") (pintype "passive"))
      (node (ref "D246") (pin "2") (pinfunction "K_2") (pintype "passive"))
      (node (ref "D247") (pin "2") (pinfunction "K_2") (pintype "passive"))
      (node (ref "D248") (pin "2") (pinfunction "K_2") (pintype "passive"))
      (node (ref "D249") (pin "2") (pinfunction "K_2") (pintype "passive"))
      (node (ref "D250") (pin "2") (pinfunction "K_2") (pintype "passive"))
      (node (ref "D251") (pin "2") (pinfunction "K_2") (pintype "passive"))
      (node (ref "D252") (pin "2") (pinfunction "K_2") (pintype "passive"))
      (node (ref "D253") (pin "2") (pinfunction "K_2") (pintype "passive"))
      (node (ref "D254") (pin "2") (pinfunction "K_2") (pintype "passive"))
      (node (ref "D256") (pin "2") (pinfunction "K_2") (pintype "passive"))
      (node (ref "D269") (pin "2") (pinfunction "K_2") (pintype "passive"))
    )
    (net (code "20") (name "/row5") (class "Default")
      (node (ref "D257") (pin "2") (pinfunction "K_2") (pintype "passive"))
      (node (ref "D260") (pin "2") (pinfunction "K_2") (pintype "passive"))
      (node (ref "D262") (pin "2") (pinfunction "K_2") (pintype "passive"))
      (node (ref "D265") (pin "2") (pinfunction "K_2") (pintype "passive"))
      (node (ref "D266") (pin "2") (pinfunction "K_2") (pintype "passive"))
    )
    (net (code "21") (name "Net-(D201-A)") (class "Default")
      (node (ref "D201") (pin "1") (pinfunction "A_1") (pintype "passive"))
      (node (ref "S201") (pin "1") (pinfunction "1_1") (pintype "passive"))
    )
    (net (code "22") (name "Net-(D202-A)") (class "Default")
      (node (ref "D202") (pin "1") (pinfunction "A_1") (pintype "passive"))
      (node (ref "S202") (pin "1") (pinfunction "1_1") (pintype "passive"))
    )
    (net (code "23") (name "Net-(D203-A)") (class "Default")
      (node (ref "D203") (pin "1") (pinfunction "A_1") (pintype "passive"))
      (node (ref "S203") (pin "1") (pinfunction "1_1") (pintype "passive"))
    )
    (net (code "24") (name "Net-(D204-A)") (class "Default")
      (node (ref "D204") (pin "1") (pinfunction "A_1") (pintype "passive"))
      (node (ref "S204") (pin "1") (pinfunction "1_1") (pintype "passive"))
    )
    (net (code "25") (name "Net-(D205-A)") (class "Default")
      (node (ref "D205") (pin "1") (pinfunction "A_1") (pintype "passive"))
      (node (ref "S205") (pin "1") (pinfunction "1_1") (pintype "passive"))
    )
    (net (code "26") (name "Net-(D206-A)") (class "Default")
      (node (ref "D206") (pin "1") (pinfunction "A_1") (pintype "passive"))
      (node (ref "S206") (pin "1") (pinfunction "1_1") (pintype "passive"))
    )
    (net (code "27") (name "Net-(D207-A)") (class "Default")
      (node (ref "D207") (pin "1") (pinfunction "A_1") (pintype "passive"))
      (node (ref "S207") (pin "1") (pinfunction "1_1") (pintype "passive"))
    )
    (net (code "28") (name "Net-(D208-A)") (class "Default")
      (node (ref "D208") (pin "1") (pinfunction "A_1") (pintype "passive"))
      (node (ref "S208") (pin "1") (pinfunction "1_1") (pintype "passive"))
    )
    (net (code "29") (name "Net-(D209-A)") (class "Default")
      (node (ref "D209") (pin "1") (pinfunction "A_1") (pintype "passive"))
      (node (ref "S209") (pin "1") (pinfunction "1_1") (pintype "passive"))
    )
    (net (code "30") (name "Net-(D210-A)") (class "Default")
      (node (ref "D210") (pin "1") (pinfunction "A_1") (pintype "passive"))
      (node (ref "S210") (pin "1") (pinfunction "1_1") (pintype "passive"))
    )
    (net (code "31") (name "Net-(D211-A)") (class "Default")
      (node (ref "D211") (pin "1") (pinfunction "A_1") (pintype "passive"))
      (node (ref "S211") (pin "1") (pinfunction "1_1") (pintype "passive"))
    )
    (net (code "32") (name "Net-(D212-A)") (class "Default")
      (node (ref "D212") (pin "1") (pinfunction "A_1") (pintype "passive"))
      (node (ref "S212") (pin "1") (pinfunction "1_1") (pintype "passive"))
    )
    (net (code "33") (name "Net-(D213-A)") (class "Default")
      (node (ref "D213") (pin "1") (pinfunction "A_1") (pintype "passive"))
      (node (ref "S213") (pin "1") (pinfunction "1_1") (pintype "passive"))
    )
    (net (code "34") (name "Net-(D214-A)") (class "Default")
      (node (ref "D214") (pin "1") (pinfunction "A_1") (pintype "passive"))
      (node (ref "S214") (pin "1") (pinfunction "1_1") (pintype "passive"))
    )
    (net (code "35") (name "Net-(D215-A)") (class "Default")
      (node (ref "D215") (pin "1") (pinfunction "A_1") (pintype "passive"))
      (node (ref "S215") (pin "1") (pinfunction "1_1") (pintype "passive"))
    )
    (net (code "36") (name "Net-(D216-A)") (class "Default")
      (node (ref "D216") (pin "1") (pinfunction "A_1") (pintype "passive"))
      (node (ref "S216") (pin "1") (pinfunction "1_1") (pintype "passive"))
    )
    (net (code "37") (name "Net-(D217-A)") (class "Default")
      (node (ref "D217") (pin "1") (pinfunction "A_1") (pintype "passive"))
      (node (ref "S217") (pin "1") (pinfunction "1_1") (pintype "passive"))
    )
    (net (code "38") (name "Net-(D218-A)") (class "Default")
      (node (ref "D218") (pin "1") (pinfunction "A_1") (pintype "passive"))
      (node (ref "S218") (pin "1") (pinfunction "1_1") (pintype "passive"))
    )
    (net (code "39") (name "Net-(D219-A)") (class "Default")
      (node (ref "D219") (pin "1") (pinfunction "A_1") (pintype "passive"))
      (node (ref "S219") (pin "1") (pinfunction "1_1") (pintype "passive"))
    )
    (net (code "40") (name "Net-(D220-A)") (class "Default")
      (node (ref "D220") (pin "1") (pinfunction "A_1") (pintype "passive"))
      (node (ref "S220") (pin "1") (pinfunction "1_1") (pintype "passive"))
    )
    (net (code "41") (name "Net-(D221-A)") (class "Default")
      (node (ref "D221") (pin "1") (pinfunction "A_1") (pintype "passive"))
      (node (ref "S221") (pin "1") (pinfunction "1_1") (pintype "passive"))
    )
    (net (code "42") (name "Net-(D222-A)") (class "Default")
      (node (ref "D222") (pin "1") (pinfunction "A_1") (pintype "passive"))
      (node (ref "S222") (pin "1") (pinfunction "1_1") (pintype "passive"))
    )
    (net (code "43") (name "Net-(D223-A)") (class "Default")
      (node (ref "D223") (pin "1") (pinfunction "A_1") (pintype "passive"))
      (node (ref "S223") (pin "1") (pinfunction "1_1") (pintype "passive"))
    )
    (net (code "44") (name "Net-(D224-A)") (class "Default")
      (node (ref "D224") (pin "1") (pinfunction "A_1") (pintype "passive"))
      (node (ref "S224") (pin "1") (pinfunction "1_1") (pintype "passive"))
    )
    (net (code "45") (name "Net-(D225-A)") (class "Default")
      (node (ref "D225") (pin "1") (pinfunction "A_1") (pintype "passive"))
      (node (ref "S225") (pin "1") (pinfunction "1_1") (pintype "passive"))
    )
    (net (code "46") (name "Net-(D226-A)") (class "Default")
      (node (ref "D226") (pin "1") (pinfunction "A_1") (pintype "passive"))
      (node (ref "S226") (pin "1") (pinfunction "1_1") (pintype "passive"))
    )
    (net (code "47") (name "Net-(D227-A)") (class "Default")
      (node (ref "D227") (pin "1") (pinfunction "A_1") (pintype "passive"))
      (node (ref "S227") (pin "1") (pinfunction "1_1") (pintype "passive"))
    )
    (net (code "48") (name "Net-(D228-A)") (class "Default")
      (node (ref "D228") (pin "1") (pinfunction "A_1") (pintype "passive"))
      (node (ref "S228") (pin "1") (pinfunction "1_1") (pintype "passive"))
    )
    (net (code "49") (name "Net-(D229-A)") (class "Default")
      (node (ref "D229") (pin "1") (pinfunction "A_1") (pintype "passive"))
      (node (ref "S229") (pin "1") (pinfunction "1_1") (pintype "passive"))
    )
    (net (code "50") (name "Net-(D230-A)") (class "Default")
      (node (ref "D230") (pin "1") (pinfunction "A_1") (pintype "passive"))
      (node (ref "S230") (pin "1") (pinfunction "1_1") (pintype "passive"))
    )
    (net (code "51") (name "Net-(D231-A)") (class "Default")
      (node (ref "D231") (pin "1") (pinfunction "A_1") (pintype "passive"))
      (node (ref "S231") (pin "1") (pinfunction "1_1") (pintype "passive"))
    )
    (net (code "52") (name "Net-(D232-A)") (class "Default")
      (node (ref "D232") (pin "1") (pinfunction "A_1") (pintype "passive"))
      (node (ref "S232") (pin "1") (pinfunction "1_1") (pintype "passive"))
    )
    (net (code "53") (name "Net-(D233-A)") (class "Default")
      (node (ref "D233") (pin "1") (pinfunction "A_1") (pintype "passive"))
      (node (ref "S233") (pin "1") (pinfunction "1_1") (pintype "passive"))
    )
    (net (code "54") (name "Net-(D234-A)") (class "Default")
      (node (ref "D234") (pin "1") (pinfunction "A_1") (pintype "passive"))
      (node (ref "S234") (pin "1") (pinfunction "1_1") (pintype "passive"))
    )
    (net (code "55") (name "Net-(D235-A)") (class "Default")
      (node (ref "D235") (pin "1") (pinfunction "A_1") (pintype "passive"))
      (node (ref "S235") (pin "1") (pinfunction "1_1") (pintype "passive"))
    )
    (net (code "56") (name "Net-(D236-A)") (class "Default")
      (node (ref "D236") (pin "1") (pinfunction "A_1") (pintype "passive"))
      (node (ref "S236") (pin "1") (pinfunction "1_1") (pintype "passive"))
    )
    (net (code "57") (name "Net-(D237-A)") (class "Default")
      (node (ref "D237") (pin "1") (pinfunction "A_1") (pintype "passive"))
      (node (ref "S237") (pin "1") (pinfunction "1_1") (pintype "passive"))
    )
    (net (code "58") (name "Net-(D238-A)") (class "Default")
      (node (ref "D238") (pin "1") (pinfunction "A_1") (pintype "passive"))
      (node (ref "S238") (pin "1") (pinfunction "1_1") (pintype "passive"))
    )
    (net (code "59") (name "Net-(D239-A)") (class "Default")
      (node (ref "D239") (pin "1") (pinfunction "A_1") (pintype "passive"))
      (node (ref "S239") (pin "1") (pinfunction "1_1") (pintype "passive"))
    )
    (net (code "60") (name "Net-(D240-A)") (class "Default")
      (node (ref "D240") (pin "1") (pinfunction "A_1") (pintype "passive"))
      (node (ref "S240") (pin "1") (pinfunction "1_1") (pintype "passive"))
    )
    (net (code "61") (name "Net-(D242-A)") (class "Default")
      (node (ref "D242") (pin "1") (pinfunction "A_1") (pintype "passive"))
      (node (ref "S242") (pin "1") (pinfunction "1_1") (pintype "passive"))
    )
    (net (code "62") (name "Net-(D243-A)") (class "Default")
      (node (ref "D243") (pin "1") (pinfunction "A_1") (pintype "passive"))
      (node (ref "S243") (pin "1") (pinfunction "1_1") (pintype "passive"))
    )
    (net (code "63") (name "Net-(D245-A)") (class "Default")
      (node (ref "D245") (pin "1") (pinfunction "A_1") (pintype "passive"))
      (node (ref "S245") (pin "1") (pinfunction "1_1") (pintype "passive"))
    )
    (net (code "64") (name "Net-(D246-A)") (class "Default")
      (node (ref "D246") (pin "1") (pinfunction "A_1") (pintype "passive"))
      (node (ref "S246") (pin "1") (pinfunction "1_1") (pintype "passive"))
    )
    (net (code "65") (name "Net-(D247-A)") (class "Default")
      (node (ref "D247") (pin "1") (pinfunction "A_1") (pintype "passive"))
      (node (ref "S247") (pin "1") (pinfunction "1_1") (pintype "passive"))
    )
    (net (code "66") (name "Net-(D248-A)") (class "Default")
      (node (ref "D248") (pin "1") (pinfunction "A_1") (pintype "passive"))
      (node (ref "S248") (pin "1") (pinfunction "1_1") (pintype "passive"))
    )
    (net (code "67") (name "Net-(D249-A)") (class "Default")
      (node (ref "D249") (pin "1") (pinfunction "A_1") (pintype "passive"))
      (node (ref "S249") (pin "1") (pinfunction "1_1") (pintype "passive"))
    )
    (net (code "68") (name "Net-(D250-A)") (class "Default")
      (node (ref "D250") (pin "1") (pinfunction "A_1") (pintype "passive"))
      (node (ref "S250") (pin "1") (pinfunction "1_1") (pintype "passive"))
    )
    (net (code "69") (name "Net-(D251-A)") (class "Default")
      (node (ref "D251") (pin "1") (pinfunction "A_1") (pintype "passive"))
      (node (ref "S251") (pin "1") (pinfunction "1_1") (pintype "passive"))
    )
    (net (code "70") (name "Net-(D252-A)") (class "Default")
      (node (ref "D252") (pin "1") (pinfunction "A_1") (pintype "passive"))
      (node (ref "S252") (pin "1") (pinfunction "1_1") (pintype "passive"))
    )
    (net (code "71") (name "Net-(D253-A)") (class "Default")
      (node (ref "D253") (pin "1") (pinfunction "A_1") (pintype "passive"))
      (node (ref "S253") (pin "1") (pinfunction "1_1") (pintype "passive"))
    )
    (net (code "72") (name "Net-(D254-A)") (class "Default")
      (node (ref "D254") (pin "1") (pinfunction "A_1") (pintype "passive"))
      (node (ref "S254") (pin "1") (pinfunction "1_1") (pintype "passive"))
    )
    (net (code "73") (name "Net-(D256-A)") (class "Default")
      (node (ref "D256") (pin "1") (pinfunction "A_1") (pintype "passive"))
      (node (ref "S256") (pin "1") (pinfunction "1_1") (pintype "passive"))
    )
    (net (code "74") (name "Net-(D257-A)") (class "Default")
      (node (ref "D257") (pin "1") (pinfunction "A_1") (pintype "passive"))
      (node (ref "S257") (pin "1") (pinfunction "1_1") (pintype "passive"))
    )
    (net (code "75") (name "Net-(D259-A)") (class "Default")
      (node (ref "D259") (pin "1") (pinfunction "A_1") (pintype "passive"))
      (node (ref "S259") (pin "1") (pinfunction "1_1") (pintype "passive"))
    )
    (net (code "76") (name "Net-(D260-A)") (class "Default")
      (node (ref "D260") (pin "1") (pinfunction "A_1") (pintype "passive"))
      (node (ref "S260") (pin "1") (pinfunction "1_1") (pintype "passive"))
    )
    (net (code "77") (name "Net-(D262-A)") (class "Default")
      (node (ref "D262") (pin "1") (pinfunction "A_1") (pintype "passive"))
      (node (ref "S262") (pin "1") (pinfunction "1_1") (pintype "passive"))
    )
    (net (code "78") (name "Net-(D265-A)") (class "Default")
      (node (ref "D265") (pin "1") (pinfunction "A_1") (pintype "passive"))
      (node (ref "S265") (pin "1") (pinfunction "1_1") (pintype "passive"))
    )
    (net (code "79") (name "Net-(D266-A)") (class "Default")
      (node (ref "D266") (pin "1") (pinfunction "A_1") (pintype "passive"))
      (node (ref "S266") (pin "1") (pinfunction "1_1") (pintype "passive"))
    )
    (net (code "80") (name "Net-(D269-A)") (class "Default")
      (node (ref "D269") (pin "1") (pinfunction "A_1") (pintype "passive"))
      (node (ref "S269") (pin "1") (pinfunction "1_1") (pintype "passive"))
    )
  )
)
